# Current_sensors.net
KiCad netlist of a schematic drawn in EAGLE
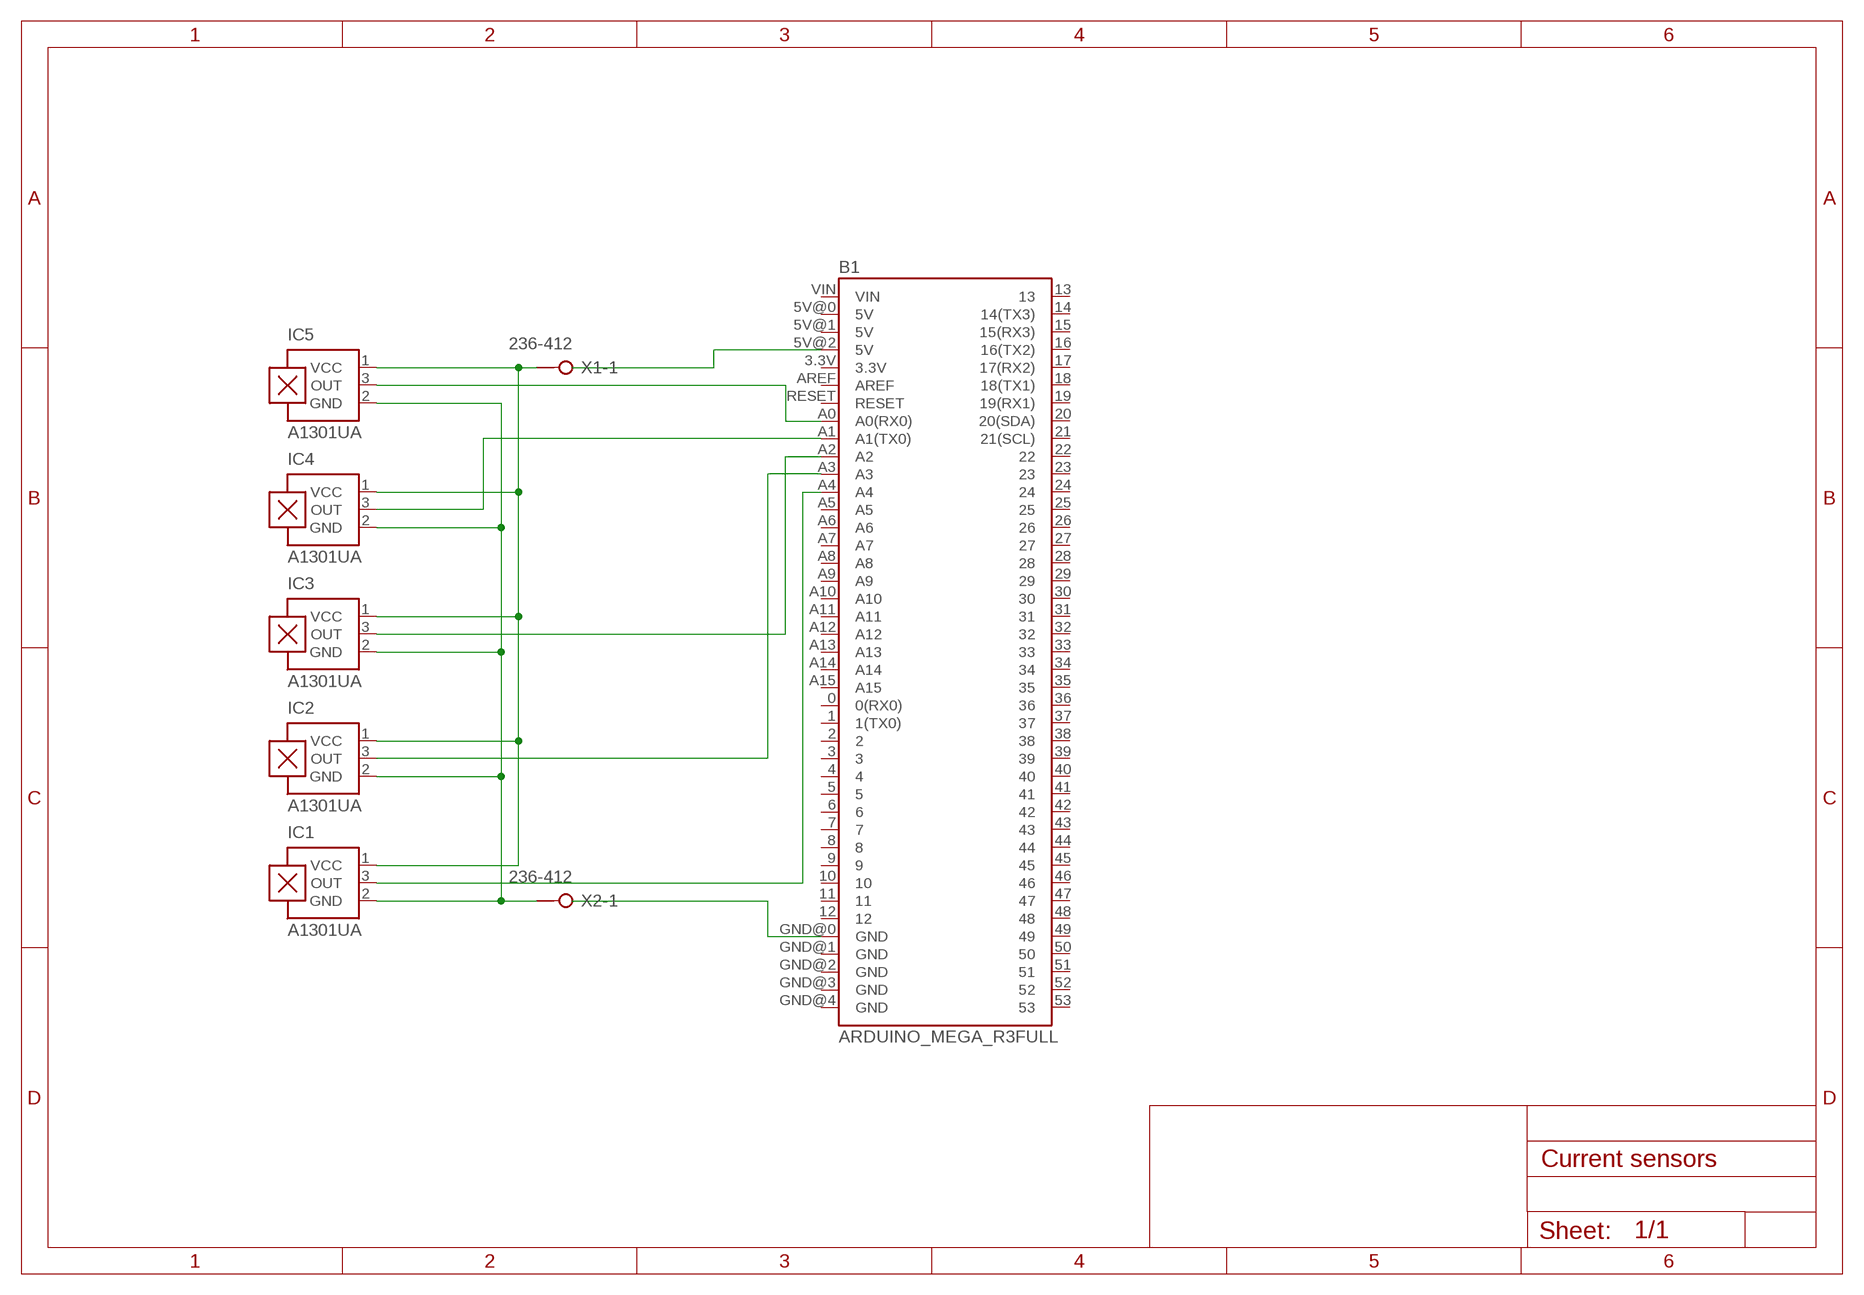
[diagram p0: schematic, sheet 1]

(export (version "E")
  (design (tool "Eeschema 10.0.6"))
  (components
    (comp (ref "B1")
      (value "ARDUINO_MEGA_R3FULL")
      (footprint "eagle-import:ARDUINO_MEGA")
      (libsource (lib "eagle-import") (part "ARDUINO_MEGA_R3FULL"))
    )
    (comp (ref "IC1")
      (value "A1301UA")
      (footprint "eagle-import:SIP3-UA")
      (fields (field (name "MF") "ALLEGRO MICROSYSTEMS, INC.") (field (name "MPN") "A1301EUA-T"))
      (libsource (lib "eagle-import") (part "A13?UA01"))
    )
    (comp (ref "IC2")
      (value "A1301UA")
      (footprint "eagle-import:SIP3-UA")
      (fields (field (name "MF") "ALLEGRO MICROSYSTEMS, INC.") (field (name "MPN") "A1301EUA-T"))
      (libsource (lib "eagle-import") (part "A13?UA01"))
    )
    (comp (ref "IC3")
      (value "A1301UA")
      (footprint "eagle-import:SIP3-UA")
      (fields (field (name "MF") "ALLEGRO MICROSYSTEMS, INC.") (field (name "MPN") "A1301EUA-T"))
      (libsource (lib "eagle-import") (part "A13?UA01"))
    )
    (comp (ref "IC4")
      (value "A1301UA")
      (footprint "eagle-import:SIP3-UA")
      (fields (field (name "MF") "ALLEGRO MICROSYSTEMS, INC.") (field (name "MPN") "A1301EUA-T"))
      (libsource (lib "eagle-import") (part "A13?UA01"))
    )
    (comp (ref "IC5")
      (value "A1301UA")
      (footprint "eagle-import:SIP3-UA")
      (fields (field (name "MF") "ALLEGRO MICROSYSTEMS, INC.") (field (name "MPN") "A1301EUA-T"))
      (libsource (lib "eagle-import") (part "A13?UA01"))
    )
    (comp (ref "X1")
      (value "236-412")
      (footprint "eagle-import:236-412")
      (fields (field (name "MF") "Wago Corporation") (field (name "MPN") "0236-0412"))
      (libsource (lib "eagle-import") (part "236-412"))
    )
    (comp (ref "X2")
      (value "236-412")
      (footprint "eagle-import:236-412")
      (fields (field (name "MF") "Wago Corporation") (field (name "MPN") "0236-0412"))
      (libsource (lib "eagle-import") (part "236-412"))
    )
  )
  (nets
    (net (code "1") (name "Net-(B1-A0(RX0))") (class "Default")
      (node (ref "B1") (pin "A0") (pinfunction "A0(RX0)_A0") (pintype "bidirectional"))
      (node (ref "IC5") (pin "3") (pinfunction "OUT_3") (pintype "output"))
    )
    (net (code "2") (name "Net-(B1-A1(TX0))") (class "Default")
      (node (ref "B1") (pin "A1") (pinfunction "A1(TX0)_A1") (pintype "bidirectional"))
      (node (ref "IC4") (pin "3") (pinfunction "OUT_3") (pintype "output"))
    )
    (net (code "3") (name "Net-(IC1-GND)") (class "Default")
      (node (ref "IC1") (pin "2") (pinfunction "GND_2") (pintype "power_in"))
      (node (ref "IC2") (pin "2") (pinfunction "GND_2") (pintype "power_in"))
      (node (ref "IC3") (pin "2") (pinfunction "GND_2") (pintype "power_in"))
      (node (ref "IC4") (pin "2") (pinfunction "GND_2") (pintype "power_in"))
      (node (ref "IC5") (pin "2") (pinfunction "GND_2") (pintype "power_in"))
      (node (ref "X2") (pin "1@1") (pinfunction "KL1_1@1") (pintype "passive"))
    )
    (net (code "4") (name "Net-(IC1-OUT)") (class "Default")
      (node (ref "B1") (pin "A4") (pinfunction "A4_A4") (pintype "bidirectional"))
      (node (ref "IC1") (pin "3") (pinfunction "OUT_3") (pintype "output"))
    )
    (net (code "5") (name "Net-(IC1-VCC)") (class "Default")
      (node (ref "IC1") (pin "1") (pinfunction "VCC_1") (pintype "power_in"))
      (node (ref "IC2") (pin "1") (pinfunction "VCC_1") (pintype "power_in"))
      (node (ref "IC3") (pin "1") (pinfunction "VCC_1") (pintype "power_in"))
      (node (ref "IC4") (pin "1") (pinfunction "VCC_1") (pintype "power_in"))
      (node (ref "IC5") (pin "1") (pinfunction "VCC_1") (pintype "power_in"))
      (node (ref "X1") (pin "1@1") (pinfunction "KL1_1@1") (pintype "passive"))
    )
    (net (code "6") (name "Net-(IC2-OUT)") (class "Default")
      (node (ref "B1") (pin "A3") (pinfunction "A3_A3") (pintype "bidirectional"))
      (node (ref "IC2") (pin "3") (pinfunction "OUT_3") (pintype "output"))
    )
    (net (code "7") (name "Net-(IC3-OUT)") (class "Default")
      (node (ref "B1") (pin "A2") (pinfunction "A2_A2") (pintype "bidirectional"))
      (node (ref "IC3") (pin "3") (pinfunction "OUT_3") (pintype "output"))
    )
    (net (code "8") (name "unconnected-(B1-0(RX0)-Pad0)") (class "Default")
      (node (ref "B1") (pin "0") (pinfunction "0(RX0)_0") (pintype "bidirectional"))
    )
    (net (code "9") (name "unconnected-(B1-1(TX0)-Pad1)") (class "Default")
      (node (ref "B1") (pin "1") (pinfunction "1(TX0)_1") (pintype "bidirectional"))
    )
    (net (code "10") (name "unconnected-(B1-5V-Pad5V@0)") (class "Default")
      (node (ref "B1") (pin "5V@0") (pinfunction "5V_5V@0") (pintype "bidirectional"))
    )
    (net (code "11") (name "unconnected-(B1-5V-Pad5V@1)") (class "Default")
      (node (ref "B1") (pin "5V@1") (pinfunction "5V_5V@1") (pintype "bidirectional"))
    )
    (net (code "12") (name "unconnected-(B1-5V-Pad5V@2)") (class "Default")
      (node (ref "B1") (pin "5V@2") (pinfunction "5V_5V@2") (pintype "bidirectional"))
    )
    (net (code "13") (name "unconnected-(B1-14(TX3)-Pad14)") (class "Default")
      (node (ref "B1") (pin "14") (pinfunction "14(TX3)_14") (pintype "bidirectional"))
    )
    (net (code "14") (name "unconnected-(B1-15(RX3)-Pad15)") (class "Default")
      (node (ref "B1") (pin "15") (pinfunction "15(RX3)_15") (pintype "bidirectional"))
    )
    (net (code "15") (name "unconnected-(B1-16(TX2)-Pad16)") (class "Default")
      (node (ref "B1") (pin "16") (pinfunction "16(TX2)_16") (pintype "bidirectional"))
    )
    (net (code "16") (name "unconnected-(B1-17(RX2)-Pad17)") (class "Default")
      (node (ref "B1") (pin "17") (pinfunction "17(RX2)_17") (pintype "bidirectional"))
    )
    (net (code "17") (name "unconnected-(B1-18(TX1)-Pad18)") (class "Default")
      (node (ref "B1") (pin "18") (pinfunction "18(TX1)_18") (pintype "bidirectional"))
    )
    (net (code "18") (name "unconnected-(B1-19(RX1)-Pad19)") (class "Default")
      (node (ref "B1") (pin "19") (pinfunction "19(RX1)_19") (pintype "bidirectional"))
    )
    (net (code "19") (name "unconnected-(B1-20(SDA)-Pad20)") (class "Default")
      (node (ref "B1") (pin "20") (pinfunction "20(SDA)_20") (pintype "bidirectional"))
    )
    (net (code "20") (name "unconnected-(B1-21(SCL)-Pad21)") (class "Default")
      (node (ref "B1") (pin "21") (pinfunction "21(SCL)_21") (pintype "bidirectional"))
    )
    (net (code "21") (name "unconnected-(B1-GND-PadGND@0)") (class "Default")
      (node (ref "B1") (pin "GND@0") (pinfunction "GND_GND@0") (pintype "bidirectional"))
    )
    (net (code "22") (name "unconnected-(B1-GND-PadGND@1)") (class "Default")
      (node (ref "B1") (pin "GND@1") (pinfunction "GND_GND@1") (pintype "bidirectional"))
    )
    (net (code "23") (name "unconnected-(B1-GND-PadGND@2)") (class "Default")
      (node (ref "B1") (pin "GND@2") (pinfunction "GND_GND@2") (pintype "bidirectional"))
    )
    (net (code "24") (name "unconnected-(B1-GND-PadGND@3)") (class "Default")
      (node (ref "B1") (pin "GND@3") (pinfunction "GND_GND@3") (pintype "bidirectional"))
    )
    (net (code "25") (name "unconnected-(B1-GND-PadGND@4)") (class "Default")
      (node (ref "B1") (pin "GND@4") (pinfunction "GND_GND@4") (pintype "bidirectional"))
    )
    (net (code "26") (name "unconnected-(B1-Pad2)") (class "Default")
      (node (ref "B1") (pin "2") (pinfunction "2_2") (pintype "bidirectional"))
    )
    (net (code "27") (name "unconnected-(B1-Pad3)") (class "Default")
      (node (ref "B1") (pin "3") (pinfunction "3_3") (pintype "bidirectional"))
    )
    (net (code "28") (name "unconnected-(B1-Pad3.3V)") (class "Default")
      (node (ref "B1") (pin "3.3V") (pinfunction "3.3V_3.3V") (pintype "bidirectional"))
    )
    (net (code "29") (name "unconnected-(B1-Pad4)") (class "Default")
      (node (ref "B1") (pin "4") (pinfunction "4_4") (pintype "bidirectional"))
    )
    (net (code "30") (name "unconnected-(B1-Pad5)") (class "Default")
      (node (ref "B1") (pin "5") (pinfunction "5_5") (pintype "bidirectional"))
    )
    (net (code "31") (name "unconnected-(B1-Pad6)") (class "Default")
      (node (ref "B1") (pin "6") (pinfunction "6_6") (pintype "bidirectional"))
    )
    (net (code "32") (name "unconnected-(B1-Pad7)") (class "Default")
      (node (ref "B1") (pin "7") (pinfunction "7_7") (pintype "bidirectional"))
    )
    (net (code "33") (name "unconnected-(B1-Pad8)") (class "Default")
      (node (ref "B1") (pin "8") (pinfunction "8_8") (pintype "bidirectional"))
    )
    (net (code "34") (name "unconnected-(B1-Pad9)") (class "Default")
      (node (ref "B1") (pin "9") (pinfunction "9_9") (pintype "bidirectional"))
    )
    (net (code "35") (name "unconnected-(B1-Pad10)") (class "Default")
      (node (ref "B1") (pin "10") (pinfunction "10_10") (pintype "bidirectional"))
    )
    (net (code "36") (name "unconnected-(B1-Pad11)") (class "Default")
      (node (ref "B1") (pin "11") (pinfunction "11_11") (pintype "bidirectional"))
    )
    (net (code "37") (name "unconnected-(B1-Pad12)") (class "Default")
      (node (ref "B1") (pin "12") (pinfunction "12_12") (pintype "bidirectional"))
    )
    (net (code "38") (name "unconnected-(B1-Pad13)") (class "Default")
      (node (ref "B1") (pin "13") (pinfunction "13_13") (pintype "bidirectional"))
    )
    (net (code "39") (name "unconnected-(B1-Pad22)") (class "Default")
      (node (ref "B1") (pin "22") (pinfunction "22_22") (pintype "bidirectional"))
    )
    (net (code "40") (name "unconnected-(B1-Pad23)") (class "Default")
      (node (ref "B1") (pin "23") (pinfunction "23_23") (pintype "bidirectional"))
    )
    (net (code "41") (name "unconnected-(B1-Pad24)") (class "Default")
      (node (ref "B1") (pin "24") (pinfunction "24_24") (pintype "bidirectional"))
    )
    (net (code "42") (name "unconnected-(B1-Pad25)") (class "Default")
      (node (ref "B1") (pin "25") (pinfunction "25_25") (pintype "bidirectional"))
    )
    (net (code "43") (name "unconnected-(B1-Pad26)") (class "Default")
      (node (ref "B1") (pin "26") (pinfunction "26_26") (pintype "bidirectional"))
    )
    (net (code "44") (name "unconnected-(B1-Pad27)") (class "Default")
      (node (ref "B1") (pin "27") (pinfunction "27_27") (pintype "bidirectional"))
    )
    (net (code "45") (name "unconnected-(B1-Pad28)") (class "Default")
      (node (ref "B1") (pin "28") (pinfunction "28_28") (pintype "bidirectional"))
    )
    (net (code "46") (name "unconnected-(B1-Pad29)") (class "Default")
      (node (ref "B1") (pin "29") (pinfunction "29_29") (pintype "bidirectional"))
    )
    (net (code "47") (name "unconnected-(B1-Pad30)") (class "Default")
      (node (ref "B1") (pin "30") (pinfunction "30_30") (pintype "bidirectional"))
    )
    (net (code "48") (name "unconnected-(B1-Pad31)") (class "Default")
      (node (ref "B1") (pin "31") (pinfunction "31_31") (pintype "bidirectional"))
    )
    (net (code "49") (name "unconnected-(B1-Pad32)") (class "Default")
      (node (ref "B1") (pin "32") (pinfunction "32_32") (pintype "bidirectional"))
    )
    (net (code "50") (name "unconnected-(B1-Pad33)") (class "Default")
      (node (ref "B1") (pin "33") (pinfunction "33_33") (pintype "bidirectional"))
    )
    (net (code "51") (name "unconnected-(B1-Pad34)") (class "Default")
      (node (ref "B1") (pin "34") (pinfunction "34_34") (pintype "bidirectional"))
    )
    (net (code "52") (name "unconnected-(B1-Pad35)") (class "Default")
      (node (ref "B1") (pin "35") (pinfunction "35_35") (pintype "bidirectional"))
    )
    (net (code "53") (name "unconnected-(B1-Pad36)") (class "Default")
      (node (ref "B1") (pin "36") (pinfunction "36_36") (pintype "bidirectional"))
    )
    (net (code "54") (name "unconnected-(B1-Pad37)") (class "Default")
      (node (ref "B1") (pin "37") (pinfunction "37_37") (pintype "bidirectional"))
    )
    (net (code "55") (name "unconnected-(B1-Pad38)") (class "Default")
      (node (ref "B1") (pin "38") (pinfunction "38_38") (pintype "bidirectional"))
    )
    (net (code "56") (name "unconnected-(B1-Pad39)") (class "Default")
      (node (ref "B1") (pin "39") (pinfunction "39_39") (pintype "bidirectional"))
    )
    (net (code "57") (name "unconnected-(B1-Pad40)") (class "Default")
      (node (ref "B1") (pin "40") (pinfunction "40_40") (pintype "bidirectional"))
    )
    (net (code "58") (name "unconnected-(B1-Pad41)") (class "Default")
      (node (ref "B1") (pin "41") (pinfunction "41_41") (pintype "bidirectional"))
    )
    (net (code "59") (name "unconnected-(B1-Pad42)") (class "Default")
      (node (ref "B1") (pin "42") (pinfunction "42_42") (pintype "bidirectional"))
    )
    (net (code "60") (name "unconnected-(B1-Pad43)") (class "Default")
      (node (ref "B1") (pin "43") (pinfunction "43_43") (pintype "bidirectional"))
    )
    (net (code "61") (name "unconnected-(B1-Pad44)") (class "Default")
      (node (ref "B1") (pin "44") (pinfunction "44_44") (pintype "bidirectional"))
    )
    (net (code "62") (name "unconnected-(B1-Pad45)") (class "Default")
      (node (ref "B1") (pin "45") (pinfunction "45_45") (pintype "bidirectional"))
    )
    (net (code "63") (name "unconnected-(B1-Pad46)") (class "Default")
      (node (ref "B1") (pin "46") (pinfunction "46_46") (pintype "bidirectional"))
    )
    (net (code "64") (name "unconnected-(B1-Pad47)") (class "Default")
      (node (ref "B1") (pin "47") (pinfunction "47_47") (pintype "bidirectional"))
    )
    (net (code "65") (name "unconnected-(B1-Pad48)") (class "Default")
      (node (ref "B1") (pin "48") (pinfunction "48_48") (pintype "bidirectional"))
    )
    (net (code "66") (name "unconnected-(B1-Pad49)") (class "Default")
      (node (ref "B1") (pin "49") (pinfunction "49_49") (pintype "bidirectional"))
    )
    (net (code "67") (name "unconnected-(B1-Pad50)") (class "Default")
      (node (ref "B1") (pin "50") (pinfunction "50_50") (pintype "bidirectional"))
    )
    (net (code "68") (name "unconnected-(B1-Pad51)") (class "Default")
      (node (ref "B1") (pin "51") (pinfunction "51_51") (pintype "bidirectional"))
    )
    (net (code "69") (name "unconnected-(B1-Pad52)") (class "Default")
      (node (ref "B1") (pin "52") (pinfunction "52_52") (pintype "bidirectional"))
    )
    (net (code "70") (name "unconnected-(B1-Pad53)") (class "Default")
      (node (ref "B1") (pin "53") (pinfunction "53_53") (pintype "bidirectional"))
    )
    (net (code "71") (name "unconnected-(B1-PadA5)") (class "Default")
      (node (ref "B1") (pin "A5") (pinfunction "A5_A5") (pintype "bidirectional"))
    )
    (net (code "72") (name "unconnected-(B1-PadA6)") (class "Default")
      (node (ref "B1") (pin "A6") (pinfunction "A6_A6") (pintype "bidirectional"))
    )
    (net (code "73") (name "unconnected-(B1-PadA7)") (class "Default")
      (node (ref "B1") (pin "A7") (pinfunction "A7_A7") (pintype "bidirectional"))
    )
    (net (code "74") (name "unconnected-(B1-PadA8)") (class "Default")
      (node (ref "B1") (pin "A8") (pinfunction "A8_A8") (pintype "bidirectional"))
    )
    (net (code "75") (name "unconnected-(B1-PadA9)") (class "Default")
      (node (ref "B1") (pin "A9") (pinfunction "A9_A9") (pintype "bidirectional"))
    )
    (net (code "76") (name "unconnected-(B1-PadA10)") (class "Default")
      (node (ref "B1") (pin "A10") (pinfunction "A10_A10") (pintype "bidirectional"))
    )
    (net (code "77") (name "unconnected-(B1-PadA11)") (class "Default")
      (node (ref "B1") (pin "A11") (pinfunction "A11_A11") (pintype "bidirectional"))
    )
    (net (code "78") (name "unconnected-(B1-PadA12)") (class "Default")
      (node (ref "B1") (pin "A12") (pinfunction "A12_A12") (pintype "bidirectional"))
    )
    (net (code "79") (name "unconnected-(B1-PadA13)") (class "Default")
      (node (ref "B1") (pin "A13") (pinfunction "A13_A13") (pintype "bidirectional"))
    )
    (net (code "80") (name "unconnected-(B1-PadA14)") (class "Default")
      (node (ref "B1") (pin "A14") (pinfunction "A14_A14") (pintype "bidirectional"))
    )
    (net (code "81") (name "unconnected-(B1-PadA15)") (class "Default")
      (node (ref "B1") (pin "A15") (pinfunction "A15_A15") (pintype "bidirectional"))
    )
    (net (code "82") (name "unconnected-(B1-PadAREF)") (class "Default")
      (node (ref "B1") (pin "AREF") (pinfunction "AREF_AREF") (pintype "bidirectional"))
    )
    (net (code "83") (name "unconnected-(B1-PadRESET)") (class "Default")
      (node (ref "B1") (pin "RESET") (pinfunction "RESET_RESET") (pintype "bidirectional"))
    )
    (net (code "84") (name "unconnected-(B1-PadVIN)") (class "Default")
      (node (ref "B1") (pin "VIN") (pinfunction "VIN_VIN") (pintype "bidirectional"))
    )
    (net (code "85") (name "unconnected-(X1A-KL2-Pad1@2)") (class "Default")
      (node (ref "X1") (pin "1@2") (pinfunction "KL2_1@2") (pintype "passive"))
    )
    (net (code "86") (name "unconnected-(X2A-KL2-Pad1@2)") (class "Default")
      (node (ref "X2") (pin "1@2") (pinfunction "KL2_1@2") (pintype "passive"))
    )
  )
)
